# stir-shield.net
KiCad netlist of a schematic drawn in EAGLE
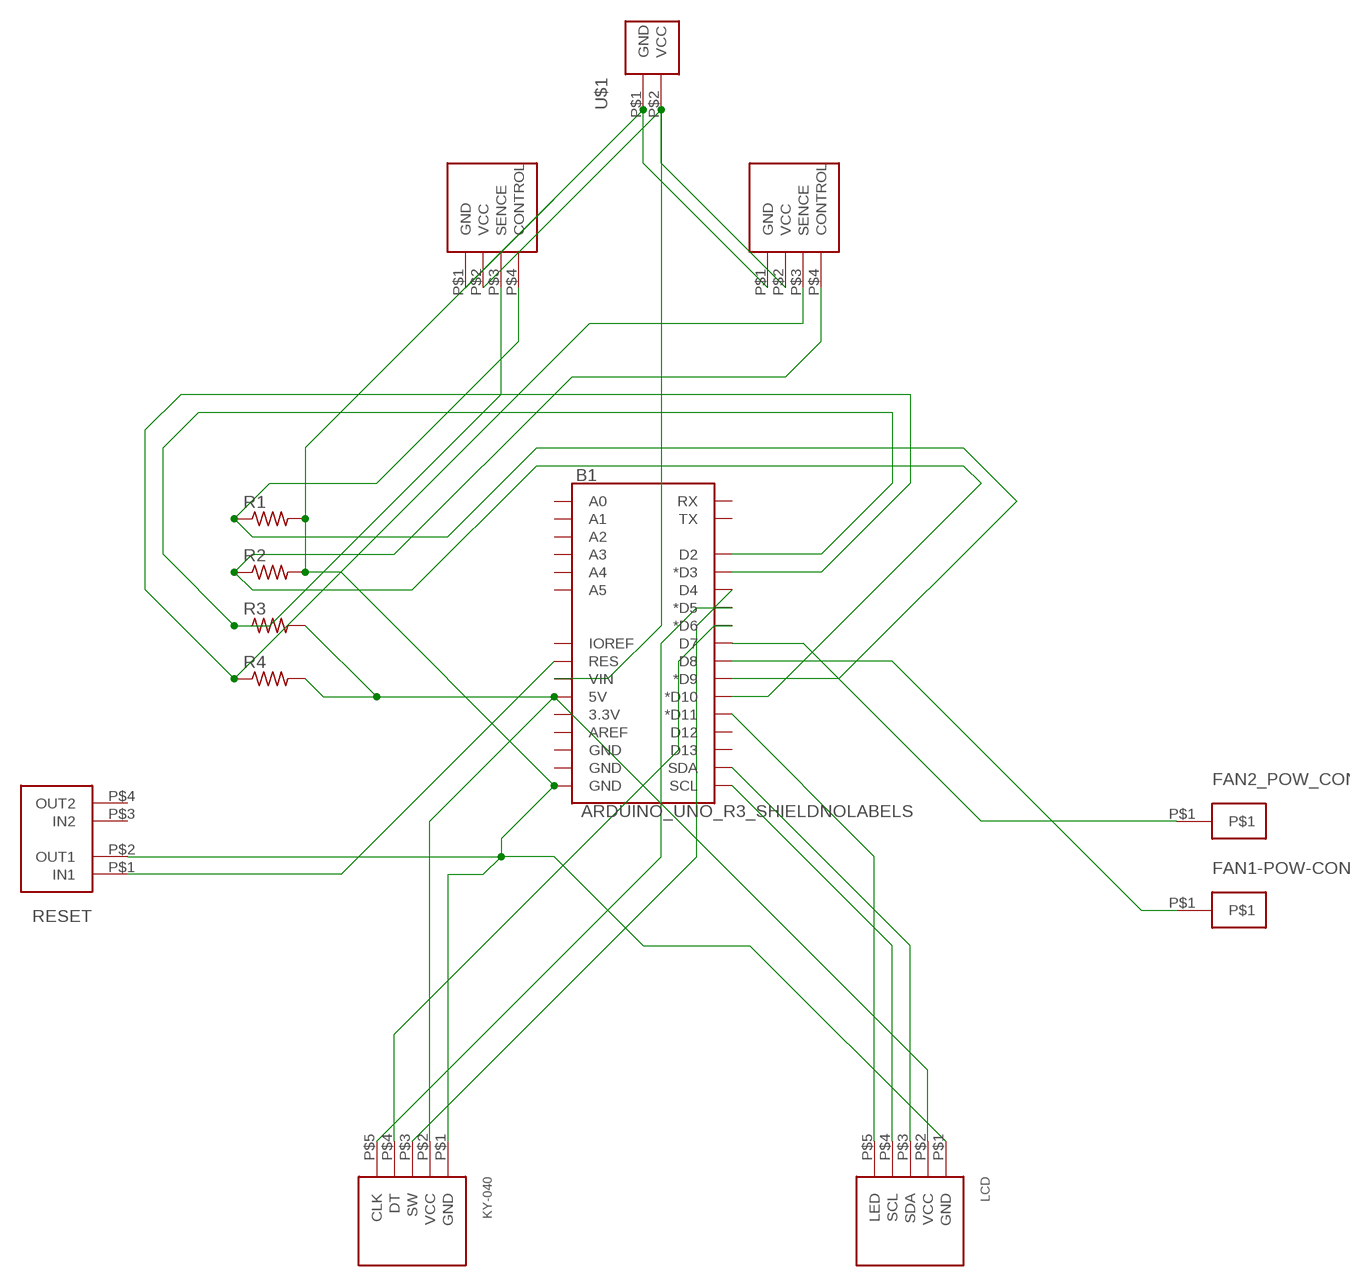
[diagram p0: schematic, sheet 1]

(export (version "E")
  (design (tool "Eeschema 10.0.6"))
  (components
    (comp (ref "B1")
      (value "ARDUINO_UNO_R3_SHIELDNOLABELS")
      (footprint "eagle-import:UNO_R3_SHIELD_NOLABELS")
      (libsource (lib "eagle-import") (part "ARDUINO_UNO_R3_SHIELDNOLABELS"))
    )
    (comp (ref "FAN1")
      (value "4PIN")
      (footprint "eagle-import:4PIN")
      (libsource (lib "eagle-import") (part "4PIN"))
    )
    (comp (ref "FAN1-POW-CON")
      (value "1PIN")
      (footprint "eagle-import:1PIN")
      (libsource (lib "eagle-import") (part "1PIN"))
    )
    (comp (ref "FAN2")
      (value "4PIN")
      (footprint "eagle-import:4PIN")
      (libsource (lib "eagle-import") (part "4PIN"))
    )
    (comp (ref "FAN2_POW_CON")
      (value "1PIN")
      (footprint "eagle-import:1PIN")
      (libsource (lib "eagle-import") (part "1PIN"))
    )
    (comp (ref "KY-040")
      (value "5PIN_KY-04")
      (footprint "eagle-import:5PIN_KY-04")
      (libsource (lib "eagle-import") (part "5PIN_KY-04"))
    )
    (comp (ref "LCD")
      (value "5PIN_LCD")
      (footprint "eagle-import:5PIN_LCD")
      (libsource (lib "eagle-import") (part "5PIN_LCD"))
    )
    (comp (ref "R1")
      (value "FLIPFLOP-RES")
      (footprint "eagle-import:0805-THM")
      (libsource (lib "eagle-import") (part "FLIPFLOP-RES"))
    )
    (comp (ref "R2")
      (value "FLIPFLOP-RES")
      (footprint "eagle-import:0805-THM")
      (libsource (lib "eagle-import") (part "FLIPFLOP-RES"))
    )
    (comp (ref "R3")
      (value "FLIPFLOP-RES")
      (footprint "eagle-import:0805-THM")
      (libsource (lib "eagle-import") (part "FLIPFLOP-RES"))
    )
    (comp (ref "R4")
      (value "FLIPFLOP-RES")
      (footprint "eagle-import:0805-THM")
      (libsource (lib "eagle-import") (part "FLIPFLOP-RES"))
    )
    (comp (ref "RESET")
      (value "BUTTON")
      (footprint "eagle-import:BUTTON")
      (libsource (lib "eagle-import") (part "BUTTON"))
    )
    (comp (ref "U$1")
      (value "2PIN")
      (footprint "eagle-import:2PIN")
      (libsource (lib "eagle-import") (part "2PIN"))
    )
  )
  (nets
    (net (code "1") (name "Net-(B1-*D3)") (class "Default")
      (node (ref "B1") (pin "D3") (pinfunction "*D3_D3") (pintype "bidirectional"))
      (node (ref "FAN2") (pin "P$3") (pinfunction "SENCE_P$3") (pintype "bidirectional"))
      (node (ref "R4") (pin "1") (pinfunction "1_1") (pintype "passive"))
    )
    (net (code "2") (name "Net-(B1-*D5)") (class "Default")
      (node (ref "B1") (pin "D5") (pinfunction "*D5_D5") (pintype "bidirectional"))
      (node (ref "KY-040") (pin "P$5") (pinfunction "CLK_P$5") (pintype "bidirectional"))
    )
    (net (code "3") (name "Net-(B1-*D6)") (class "Default")
      (node (ref "B1") (pin "D6") (pinfunction "*D6_D6") (pintype "bidirectional"))
      (node (ref "KY-040") (pin "P$4") (pinfunction "DT_P$4") (pintype "bidirectional"))
    )
    (net (code "4") (name "Net-(B1-*D9)") (class "Default")
      (node (ref "B1") (pin "D9") (pinfunction "*D9_D9") (pintype "bidirectional"))
      (node (ref "FAN1") (pin "P$4") (pinfunction "CONTROL_P$4") (pintype "bidirectional"))
      (node (ref "R1") (pin "1") (pinfunction "1_1") (pintype "passive"))
    )
    (net (code "5") (name "Net-(B1-*D10)") (class "Default")
      (node (ref "B1") (pin "D10") (pinfunction "*D10_D10") (pintype "bidirectional"))
      (node (ref "FAN2") (pin "P$4") (pinfunction "CONTROL_P$4") (pintype "bidirectional"))
      (node (ref "R2") (pin "1") (pinfunction "1_1") (pintype "passive"))
    )
    (net (code "6") (name "Net-(B1-*D11)") (class "Default")
      (node (ref "B1") (pin "D11") (pinfunction "*D11_D11") (pintype "bidirectional"))
      (node (ref "LCD") (pin "P$5") (pinfunction "LED_P$5") (pintype "bidirectional"))
    )
    (net (code "7") (name "Net-(B1-PadD7)") (class "Default")
      (node (ref "B1") (pin "D7") (pinfunction "D7_D7") (pintype "bidirectional"))
      (node (ref "FAN2_POW_CON") (pin "P$1") (pinfunction "P$1_P$1") (pintype "bidirectional"))
    )
    (net (code "8") (name "Net-(B1-PadD8)") (class "Default")
      (node (ref "B1") (pin "D8") (pinfunction "D8_D8") (pintype "bidirectional"))
      (node (ref "FAN1-POW-CON") (pin "P$1") (pinfunction "P$1_P$1") (pintype "bidirectional"))
    )
    (net (code "9") (name "Net-(FAN1-GND)") (class "Default")
      (node (ref "B1") (pin "GND@0") (pinfunction "GND_GND@0") (pintype "bidirectional"))
      (node (ref "FAN1") (pin "P$1") (pinfunction "GND_P$1") (pintype "bidirectional"))
      (node (ref "FAN2") (pin "P$1") (pinfunction "GND_P$1") (pintype "bidirectional"))
      (node (ref "KY-040") (pin "P$1") (pinfunction "GND_P$1") (pintype "bidirectional"))
      (node (ref "LCD") (pin "P$1") (pinfunction "GND_P$1") (pintype "bidirectional"))
      (node (ref "R1") (pin "2") (pinfunction "2_2") (pintype "passive"))
      (node (ref "R2") (pin "2") (pinfunction "2_2") (pintype "passive"))
      (node (ref "RESET") (pin "P$2") (pinfunction "OUT1_P$2") (pintype "bidirectional"))
      (node (ref "U$1") (pin "P$1") (pinfunction "GND_P$1") (pintype "bidirectional"))
    )
    (net (code "10") (name "Net-(FAN1-SENCE)") (class "Default")
      (node (ref "B1") (pin "D2") (pinfunction "D2_D2") (pintype "bidirectional"))
      (node (ref "FAN1") (pin "P$3") (pinfunction "SENCE_P$3") (pintype "bidirectional"))
      (node (ref "R3") (pin "1") (pinfunction "1_1") (pintype "passive"))
    )
    (net (code "11") (name "Net-(FAN1-VCC)") (class "Default")
      (node (ref "B1") (pin "VIN") (pinfunction "VIN_VIN") (pintype "bidirectional"))
      (node (ref "FAN1") (pin "P$2") (pinfunction "VCC_P$2") (pintype "bidirectional"))
      (node (ref "FAN2") (pin "P$2") (pinfunction "VCC_P$2") (pintype "bidirectional"))
      (node (ref "U$1") (pin "P$2") (pinfunction "VCC_P$2") (pintype "bidirectional"))
    )
    (net (code "12") (name "Net-(KY-040-SW)") (class "Default")
      (node (ref "B1") (pin "D4") (pinfunction "D4_D4") (pintype "bidirectional"))
      (node (ref "KY-040") (pin "P$3") (pinfunction "SW_P$3") (pintype "bidirectional"))
    )
    (net (code "13") (name "Net-(KY-040-VCC)") (class "Default")
      (node (ref "B1") (pin "5V") (pinfunction "5V_5V") (pintype "bidirectional"))
      (node (ref "KY-040") (pin "P$2") (pinfunction "VCC_P$2") (pintype "bidirectional"))
      (node (ref "LCD") (pin "P$2") (pinfunction "VCC_P$2") (pintype "bidirectional"))
      (node (ref "R3") (pin "2") (pinfunction "2_2") (pintype "passive"))
      (node (ref "R4") (pin "2") (pinfunction "2_2") (pintype "passive"))
    )
    (net (code "14") (name "Net-(LCD-SCL)") (class "Default")
      (node (ref "B1") (pin "SCL") (pinfunction "SCL_SCL") (pintype "bidirectional"))
      (node (ref "LCD") (pin "P$4") (pinfunction "SCL_P$4") (pintype "bidirectional"))
    )
    (net (code "15") (name "Net-(LCD-SDA)") (class "Default")
      (node (ref "B1") (pin "SDA") (pinfunction "SDA_SDA") (pintype "bidirectional"))
      (node (ref "LCD") (pin "P$3") (pinfunction "SDA_P$3") (pintype "bidirectional"))
    )
    (net (code "16") (name "Net-(RESET-IN1)") (class "Default")
      (node (ref "B1") (pin "RES") (pinfunction "RES_RES") (pintype "bidirectional"))
      (node (ref "RESET") (pin "P$1") (pinfunction "IN1_P$1") (pintype "bidirectional"))
    )
    (net (code "17") (name "unconnected-(B1-GND-PadGND@1)") (class "Default")
      (node (ref "B1") (pin "GND@1") (pinfunction "GND_GND@1") (pintype "bidirectional"))
    )
    (net (code "18") (name "unconnected-(B1-GND-PadGND@2)") (class "Default")
      (node (ref "B1") (pin "GND@2") (pinfunction "GND_GND@2") (pintype "bidirectional"))
    )
    (net (code "19") (name "unconnected-(B1-Pad3.3V)") (class "Default")
      (node (ref "B1") (pin "3.3V") (pinfunction "3.3V_3.3V") (pintype "bidirectional"))
    )
    (net (code "20") (name "unconnected-(B1-PadA0)") (class "Default")
      (node (ref "B1") (pin "A0") (pinfunction "A0_A0") (pintype "bidirectional"))
    )
    (net (code "21") (name "unconnected-(B1-PadA1)") (class "Default")
      (node (ref "B1") (pin "A1") (pinfunction "A1_A1") (pintype "bidirectional"))
    )
    (net (code "22") (name "unconnected-(B1-PadA2)") (class "Default")
      (node (ref "B1") (pin "A2") (pinfunction "A2_A2") (pintype "bidirectional"))
    )
    (net (code "23") (name "unconnected-(B1-PadA3)") (class "Default")
      (node (ref "B1") (pin "A3") (pinfunction "A3_A3") (pintype "bidirectional"))
    )
    (net (code "24") (name "unconnected-(B1-PadA4)") (class "Default")
      (node (ref "B1") (pin "A4") (pinfunction "A4_A4") (pintype "bidirectional"))
    )
    (net (code "25") (name "unconnected-(B1-PadA5)") (class "Default")
      (node (ref "B1") (pin "A5") (pinfunction "A5_A5") (pintype "bidirectional"))
    )
    (net (code "26") (name "unconnected-(B1-PadAREF)") (class "Default")
      (node (ref "B1") (pin "AREF") (pinfunction "AREF_AREF") (pintype "bidirectional"))
    )
    (net (code "27") (name "unconnected-(B1-PadD12)") (class "Default")
      (node (ref "B1") (pin "D12") (pinfunction "D12_D12") (pintype "bidirectional"))
    )
    (net (code "28") (name "unconnected-(B1-PadD13)") (class "Default")
      (node (ref "B1") (pin "D13") (pinfunction "D13_D13") (pintype "bidirectional"))
    )
    (net (code "29") (name "unconnected-(B1-PadIOREF)") (class "Default")
      (node (ref "B1") (pin "IOREF") (pinfunction "IOREF_IOREF") (pintype "bidirectional"))
    )
    (net (code "30") (name "unconnected-(B1-PadRX)") (class "Default")
      (node (ref "B1") (pin "RX") (pinfunction "RX_RX") (pintype "bidirectional"))
    )
    (net (code "31") (name "unconnected-(B1-PadTX)") (class "Default")
      (node (ref "B1") (pin "TX") (pinfunction "TX_TX") (pintype "bidirectional"))
    )
    (net (code "32") (name "unconnected-(RESET-IN2-PadP$3)") (class "Default")
      (node (ref "RESET") (pin "P$3") (pinfunction "IN2_P$3") (pintype "bidirectional"))
    )
    (net (code "33") (name "unconnected-(RESET-OUT2-PadP$4)") (class "Default")
      (node (ref "RESET") (pin "P$4") (pinfunction "OUT2_P$4") (pintype "bidirectional"))
    )
  )
)
